# 11-Cooling_Sensors.net
KiCad netlist of a schematic drawn in Altium Designer
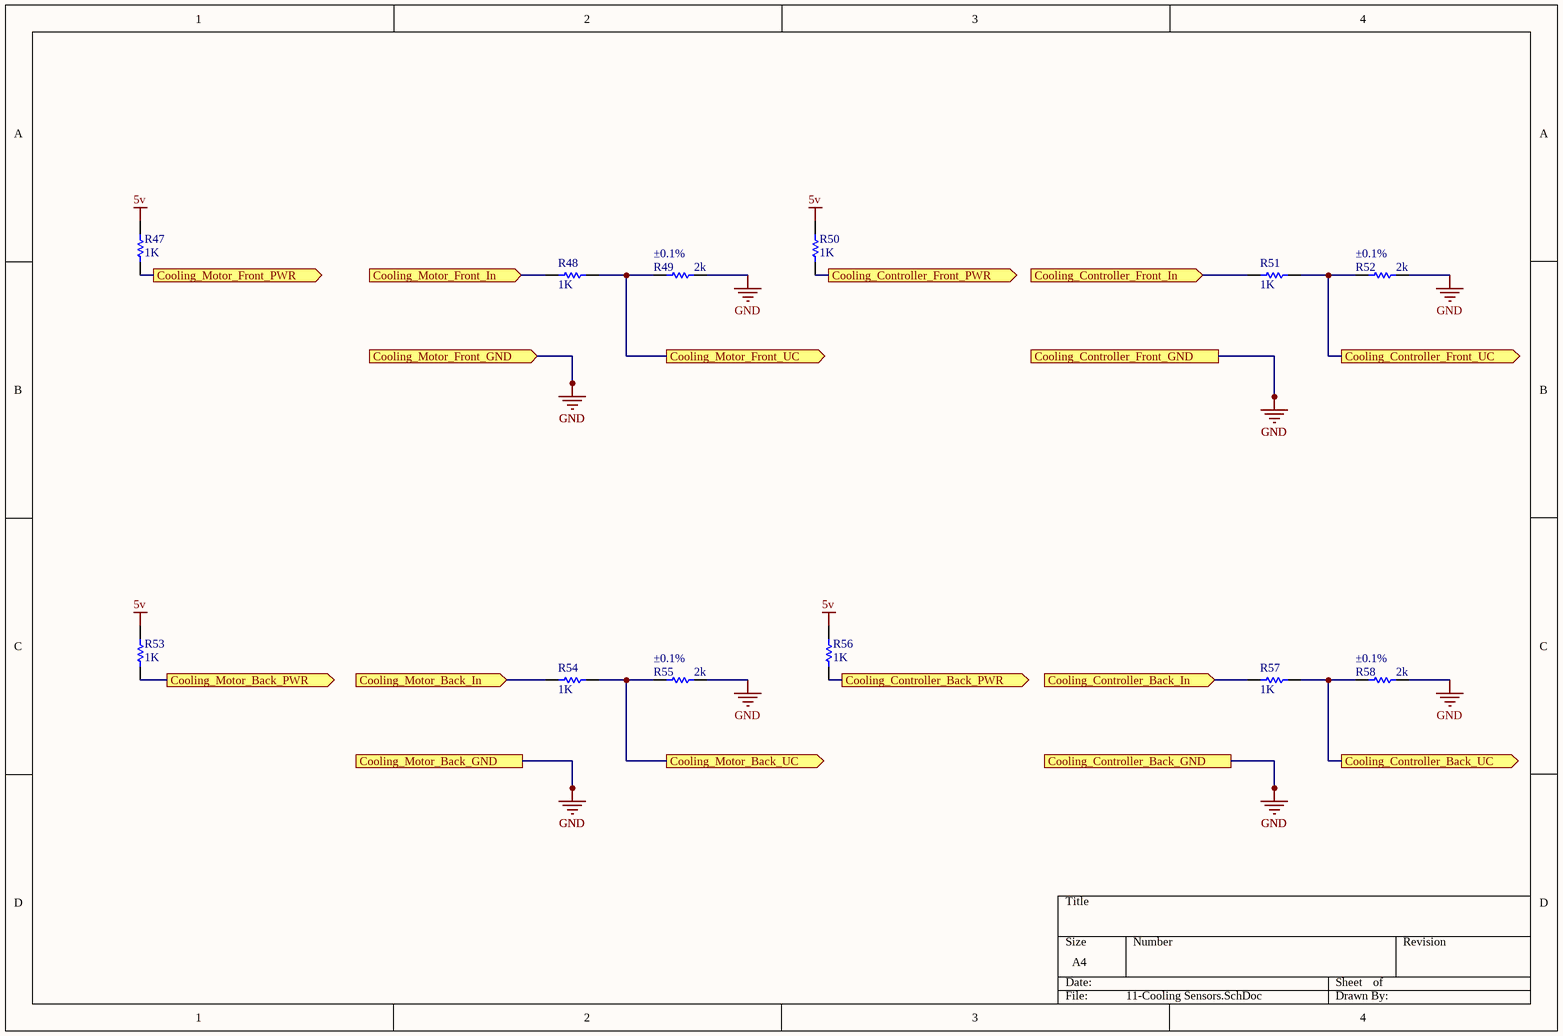
[diagram p0: 11-Cooling Sensors.SchDoc]

(export (version "E")
  (design (tool "Eeschema 10.0.6"))
  (components
    (comp (ref "R47")
      (value "1K")
      (footprint "1608[0603]")
      (description "Resistor")
      (fields (field (name "Comment") "Res1") (field (name "PUBLISHER") "Altium Limited"))
      (libsource (lib "Miscellaneous Devices") (part "Res1"))
    )
    (comp (ref "R48")
      (value "1K")
      (footprint "1608[0603]")
      (description "Resistor")
      (fields (field (name "Comment") "Res1") (field (name "PUBLISHER") "Altium Limited"))
      (libsource (lib "Miscellaneous Devices") (part "Res1"))
    )
    (comp (ref "R49")
      (value "2k")
      (footprint "1608[0603]")
      (description "Resistor")
      (fields
        (field (name "MANUFACTURER") "Yageo")
        (field (name "MANUFACTURER PART NUMBER") "AT0603BRD072KL")
        (field (name "TOLERANCE") "±0.1%")
      )
      (libsource (lib "Miscellaneous Devices") (part "Res1"))
    )
    (comp (ref "R50")
      (value "1K")
      (footprint "1608[0603]")
      (description "Resistor")
      (fields (field (name "Comment") "Res1") (field (name "PUBLISHER") "Altium Limited"))
      (libsource (lib "Miscellaneous Devices") (part "Res1"))
    )
    (comp (ref "R51")
      (value "1K")
      (footprint "1608[0603]")
      (description "Resistor")
      (fields (field (name "Comment") "Res1") (field (name "PUBLISHER") "Altium Limited"))
      (libsource (lib "Miscellaneous Devices") (part "Res1"))
    )
    (comp (ref "R52")
      (value "2k")
      (footprint "1608[0603]")
      (description "Resistor")
      (fields
        (field (name "MANUFACTURER") "Yageo")
        (field (name "MANUFACTURER PART NUMBER") "AT0603BRD072KL")
        (field (name "TOLERANCE") "±0.1%")
      )
      (libsource (lib "Miscellaneous Devices") (part "Res1"))
    )
    (comp (ref "R53")
      (value "1K")
      (footprint "1608[0603]")
      (description "Resistor")
      (fields (field (name "Comment") "Res1") (field (name "PUBLISHER") "Altium Limited"))
      (libsource (lib "Miscellaneous Devices") (part "Res1"))
    )
    (comp (ref "R54")
      (value "1K")
      (footprint "1608[0603]")
      (description "Resistor")
      (fields (field (name "Comment") "Res1") (field (name "PUBLISHER") "Altium Limited"))
      (libsource (lib "Miscellaneous Devices") (part "Res1"))
    )
    (comp (ref "R55")
      (value "2k")
      (footprint "1608[0603]")
      (description "Resistor")
      (fields
        (field (name "MANUFACTURER") "Yageo")
        (field (name "MANUFACTURER PART NUMBER") "AT0603BRD072KL")
        (field (name "TOLERANCE") "±0.1%")
      )
      (libsource (lib "Miscellaneous Devices") (part "Res1"))
    )
    (comp (ref "R56")
      (value "1K")
      (footprint "1608[0603]")
      (description "Resistor")
      (fields (field (name "Comment") "Res1") (field (name "PUBLISHER") "Altium Limited"))
      (libsource (lib "Miscellaneous Devices") (part "Res1"))
    )
    (comp (ref "R57")
      (value "1K")
      (footprint "1608[0603]")
      (description "Resistor")
      (fields (field (name "Comment") "Res1") (field (name "PUBLISHER") "Altium Limited"))
      (libsource (lib "Miscellaneous Devices") (part "Res1"))
    )
    (comp (ref "R58")
      (value "2k")
      (footprint "1608[0603]")
      (description "Resistor")
      (fields
        (field (name "MANUFACTURER") "Yageo")
        (field (name "MANUFACTURER PART NUMBER") "AT0603BRD072KL")
        (field (name "TOLERANCE") "±0.1%")
      )
      (libsource (lib "Miscellaneous Devices") (part "Res1"))
    )
  )
  (nets
    (net (code "1") (name "/Cooling_Controller_Back_In") (class "Default")
      (node (ref "R57") (pin "2") (pinfunction "2_2") (pintype "passive"))
    )
    (net (code "2") (name "/Cooling_Controller_Back_PWR") (class "Default")
      (node (ref "R56") (pin "1") (pinfunction "1_1") (pintype "passive"))
    )
    (net (code "3") (name "/Cooling_Controller_Back_UC") (class "Default")
      (node (ref "R57") (pin "1") (pinfunction "1_1") (pintype "passive"))
      (node (ref "R58") (pin "1") (pinfunction "1_1") (pintype "passive"))
    )
    (net (code "4") (name "/Cooling_Controller_Front_In") (class "Default")
      (node (ref "R51") (pin "2") (pinfunction "2_2") (pintype "passive"))
    )
    (net (code "5") (name "/Cooling_Controller_Front_PWR") (class "Default")
      (node (ref "R50") (pin "1") (pinfunction "1_1") (pintype "passive"))
    )
    (net (code "6") (name "/Cooling_Controller_Front_UC") (class "Default")
      (node (ref "R51") (pin "1") (pinfunction "1_1") (pintype "passive"))
      (node (ref "R52") (pin "1") (pinfunction "1_1") (pintype "passive"))
    )
    (net (code "7") (name "/Cooling_Motor_Back_In") (class "Default")
      (node (ref "R54") (pin "2") (pinfunction "2_2") (pintype "passive"))
    )
    (net (code "8") (name "/Cooling_Motor_Back_PWR") (class "Default")
      (node (ref "R53") (pin "1") (pinfunction "1_1") (pintype "passive"))
    )
    (net (code "9") (name "/Cooling_Motor_Back_UC") (class "Default")
      (node (ref "R54") (pin "1") (pinfunction "1_1") (pintype "passive"))
      (node (ref "R55") (pin "1") (pinfunction "1_1") (pintype "passive"))
    )
    (net (code "10") (name "/Cooling_Motor_Front_In") (class "Default")
      (node (ref "R48") (pin "2") (pinfunction "2_2") (pintype "passive"))
    )
    (net (code "11") (name "/Cooling_Motor_Front_PWR") (class "Default")
      (node (ref "R47") (pin "1") (pinfunction "1_1") (pintype "passive"))
    )
    (net (code "12") (name "/Cooling_Motor_Front_UC") (class "Default")
      (node (ref "R48") (pin "1") (pinfunction "1_1") (pintype "passive"))
      (node (ref "R49") (pin "1") (pinfunction "1_1") (pintype "passive"))
    )
    (net (code "13") (name "5v") (class "Default")
      (node (ref "R47") (pin "2") (pinfunction "2_2") (pintype "passive"))
      (node (ref "R50") (pin "2") (pinfunction "2_2") (pintype "passive"))
      (node (ref "R53") (pin "2") (pinfunction "2_2") (pintype "passive"))
      (node (ref "R56") (pin "2") (pinfunction "2_2") (pintype "passive"))
    )
    (net (code "14") (name "GND") (class "Default")
      (node (ref "R49") (pin "2") (pinfunction "2_2") (pintype "passive"))
      (node (ref "R52") (pin "2") (pinfunction "2_2") (pintype "passive"))
      (node (ref "R55") (pin "2") (pinfunction "2_2") (pintype "passive"))
      (node (ref "R58") (pin "2") (pinfunction "2_2") (pintype "passive"))
    )
  )
)
